# MCU.net
KiCad netlist of a schematic drawn in Altium Designer
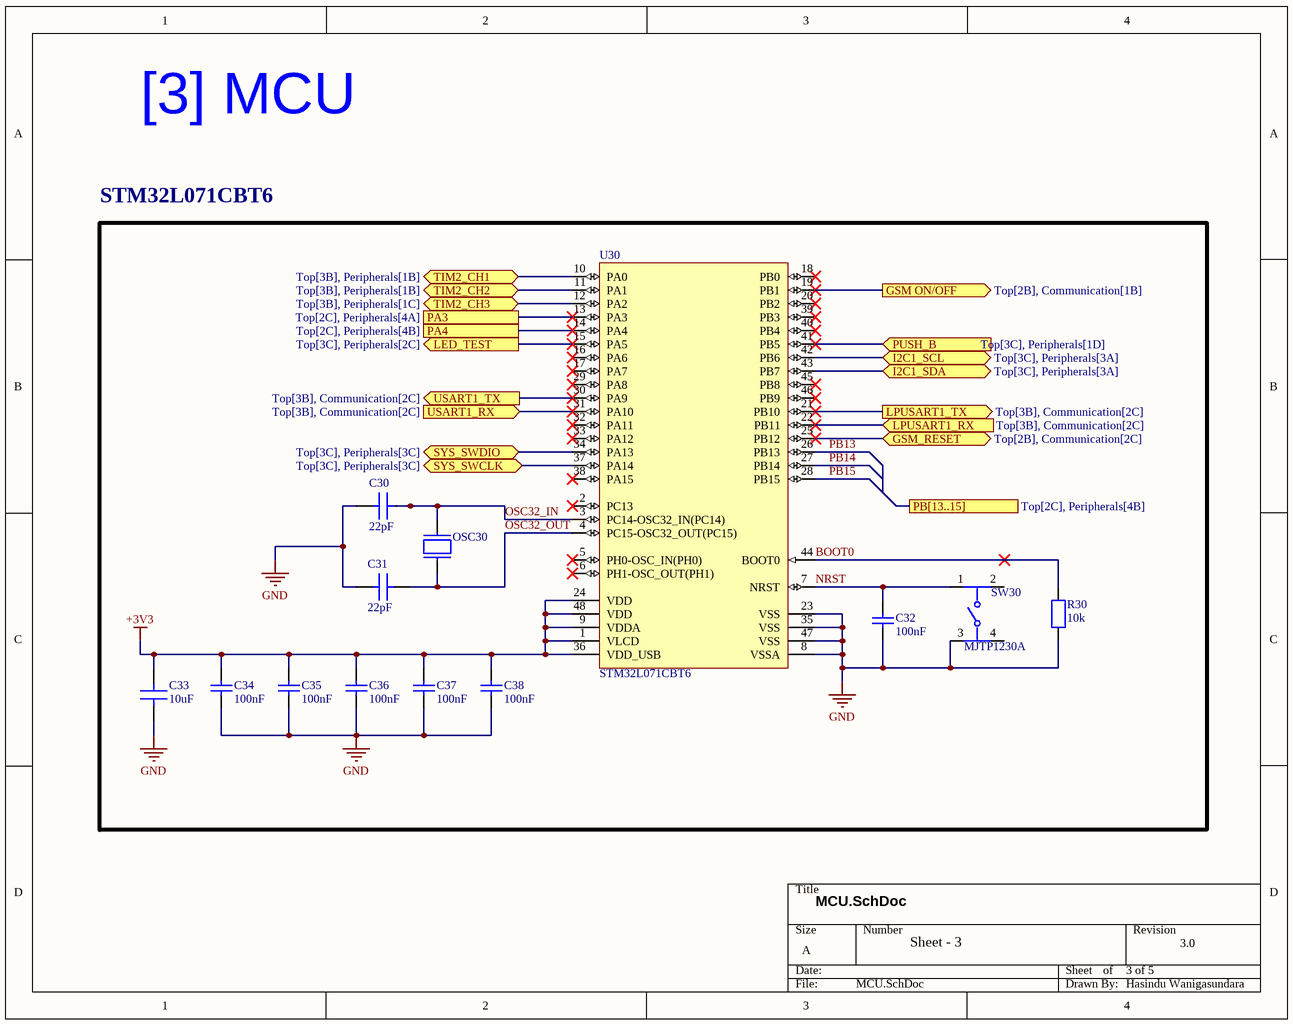
[diagram p0: MCU.SchDoc]

(export (version "E")
  (design (tool "Eeschema 10.0.6"))
  (components
    (comp (ref "C30")
      (value "22pF")
      (footprint "CAP_1206")
      (description "SMD 3.2mm × 1.6mm size capacitor (1206)")
      (libsource (lib "EDR - Water Meter") (part "CAP_1206"))
    )
    (comp (ref "C31")
      (value "22pF")
      (footprint "CAP_1206")
      (description "SMD 3.2mm × 1.6mm size capacitor (1206)")
      (libsource (lib "EDR - Water Meter") (part "CAP_1206"))
    )
    (comp (ref "C32")
      (value "100nF")
      (footprint "CAPC2013X140X50NL20T25")
      (fields
        (field (name "PART NUMBER") "0805YD105MAT2A")
        (field (name "MANUFACTURER") "AVX Interconnect / Elco")
      )
      (libsource (lib "Altium Content Vault") (part "CAP"))
    )
    (comp (ref "C33")
      (value "10uF")
      (footprint "CAP_1206")
      (description "SMD 3.2mm × 1.6mm size capacitor (1206)")
      (libsource (lib "EDR - Water Meter") (part "CAP_1206"))
    )
    (comp (ref "C34")
      (value "100nF")
      (footprint "CAPC2013X140X50NL20T25")
      (fields
        (field (name "PART NUMBER") "0805YD105MAT2A")
        (field (name "MANUFACTURER") "AVX Interconnect / Elco")
      )
      (libsource (lib "Altium Content Vault") (part "CAP"))
    )
    (comp (ref "C35")
      (value "100nF")
      (footprint "CAPC2013X140X50NL20T25")
      (fields
        (field (name "PART NUMBER") "0805YD105MAT2A")
        (field (name "MANUFACTURER") "AVX Interconnect / Elco")
      )
      (libsource (lib "Altium Content Vault") (part "CAP"))
    )
    (comp (ref "C36")
      (value "100nF")
      (footprint "CAPC2013X140X50NL20T25")
      (fields
        (field (name "PART NUMBER") "0805YD105MAT2A")
        (field (name "MANUFACTURER") "AVX Interconnect / Elco")
      )
      (libsource (lib "Altium Content Vault") (part "CAP"))
    )
    (comp (ref "C37")
      (value "100nF")
      (footprint "CAPC2013X140X50NL20T25")
      (fields
        (field (name "PART NUMBER") "0805YD105MAT2A")
        (field (name "MANUFACTURER") "AVX Interconnect / Elco")
      )
      (libsource (lib "Altium Content Vault") (part "CAP"))
    )
    (comp (ref "C38")
      (value "100nF")
      (footprint "CAPC2013X140X50NL20T25")
      (fields
        (field (name "PART NUMBER") "0805YD105MAT2A")
        (field (name "MANUFACTURER") "AVX Interconnect / Elco")
      )
      (libsource (lib "Altium Content Vault") (part "CAP"))
    )
    (comp (ref "OSC30")
      (value "CRYSTAL OSC")
      (footprint "Crystal_OSC")
      (description "CRYSTAL 32.768kHz 12.5pF SMD")
      (libsource (lib "EDR - Water Meter") (part "CRYSTAL OSC"))
    )
    (comp (ref "R30")
      (value "10k")
      (footprint "RES_1206")
      (description "SMD 3.2mm × 1.6mm size resistor (1206)")
      (libsource (lib "EDR - Water Meter") (part "RES_1206"))
    )
    (comp (ref "SW30")
      (value "MJTP1230A")
      (footprint "FP-MJTP1230A-MFG")
      (description "SWITCH TACTILE SPST-NO 0.05A 12V")
      (libsource (lib "Altium Content Vault") (part "1adf0dd01260c80cf25a44bfd6b99ba"))
    )
    (comp (ref "U30")
      (value "STM32L071CBT6")
      (footprint "STM-LQFP48_M")
      (description "ARM Cortex-M0+ 32 Bit 32MHz 37 LQFP-48(7x7) Microcontrollers RoHS")
      (libsource (lib "Altium Content Vault") (part "MC-ARM-STM32L073-LQFP48"))
    )
  )
  (nets
    (net (code "1") (name "+3V3") (class "Default")
      (node (ref "C33") (pin "2") (pintype "passive"))
      (node (ref "C34") (pin "2") (pinfunction "2_2") (pintype "passive"))
      (node (ref "C35") (pin "2") (pinfunction "2_2") (pintype "passive"))
      (node (ref "C36") (pin "2") (pinfunction "2_2") (pintype "passive"))
      (node (ref "C37") (pin "2") (pinfunction "2_2") (pintype "passive"))
      (node (ref "C38") (pin "2") (pinfunction "2_2") (pintype "passive"))
      (node (ref "U30") (pin "1") (pinfunction "VLCD_1") (pintype "power_in"))
      (node (ref "U30") (pin "24") (pinfunction "VDD_24") (pintype "power_in"))
      (node (ref "U30") (pin "36") (pinfunction "VDD_USB_36") (pintype "power_in"))
      (node (ref "U30") (pin "48") (pinfunction "VDD_48") (pintype "power_in"))
      (node (ref "U30") (pin "9") (pinfunction "VDDA_9") (pintype "power_in"))
    )
    (net (code "3") (name "/BOOT0") (class "Default")
      (node (ref "R30") (pin "1") (pintype "passive"))
      (node (ref "U30") (pin "44") (pinfunction "BOOT0_44") (pintype "input"))
    )
    (net (code "4") (name "/GSM ON{slash}OFF") (class "Default")
      (node (ref "U30") (pin "19") (pinfunction "PB1_19") (pintype "bidirectional+no_connect"))
    )
    (net (code "5") (name "/GSM_RESET") (class "Default")
      (node (ref "U30") (pin "25") (pinfunction "PB12_25") (pintype "bidirectional+no_connect"))
    )
    (net (code "6") (name "/I2C1_SCL") (class "Default")
      (node (ref "U30") (pin "42") (pinfunction "PB6_42") (pintype "bidirectional"))
    )
    (net (code "7") (name "/I2C1_SDA") (class "Default")
      (node (ref "U30") (pin "43") (pinfunction "PB7_43") (pintype "bidirectional"))
    )
    (net (code "8") (name "/LED_TEST") (class "Default")
      (node (ref "U30") (pin "15") (pinfunction "PA5_15") (pintype "bidirectional+no_connect"))
    )
    (net (code "9") (name "/LPUSART1_RX") (class "Default")
      (node (ref "U30") (pin "22") (pinfunction "PB11_22") (pintype "bidirectional+no_connect"))
    )
    (net (code "10") (name "/LPUSART1_TX") (class "Default")
      (node (ref "U30") (pin "21") (pinfunction "PB10_21") (pintype "bidirectional+no_connect"))
    )
    (net (code "11") (name "/NRST") (class "Default")
      (node (ref "C32") (pin "2") (pinfunction "2_2") (pintype "passive"))
      (node (ref "SW30") (pin "1") (pinfunction "1_1") (pintype "passive"))
      (node (ref "U30") (pin "7") (pinfunction "NRST_7") (pintype "bidirectional"))
    )
    (net (code "12") (name "/OSC32_IN") (class "Default")
      (node (ref "C30") (pin "1") (pintype "passive"))
      (node (ref "OSC30") (pin "2") (pintype "passive"))
      (node (ref "U30") (pin "3") (pinfunction "PC14-OSC32_IN(PC14)_3") (pintype "bidirectional"))
    )
    (net (code "13") (name "/OSC32_OUT") (class "Default")
      (node (ref "C31") (pin "2") (pintype "passive"))
      (node (ref "OSC30") (pin "1") (pintype "passive"))
      (node (ref "U30") (pin "4") (pinfunction "PC15-OSC32_OUT(PC15)_4") (pintype "bidirectional"))
    )
    (net (code "14") (name "/PA3") (class "Default")
      (node (ref "U30") (pin "13") (pinfunction "PA3_13") (pintype "bidirectional+no_connect"))
    )
    (net (code "15") (name "/PA4") (class "Default")
      (node (ref "U30") (pin "14") (pinfunction "PA4_14") (pintype "bidirectional+no_connect"))
    )
    (net (code "16") (name "/PB13") (class "Default")
      (node (ref "U30") (pin "26") (pinfunction "PB13_26") (pintype "bidirectional"))
    )
    (net (code "17") (name "/PB14") (class "Default")
      (node (ref "U30") (pin "27") (pinfunction "PB14_27") (pintype "bidirectional"))
    )
    (net (code "18") (name "/PB15") (class "Default")
      (node (ref "U30") (pin "28") (pinfunction "PB15_28") (pintype "bidirectional"))
    )
    (net (code "20") (name "/PUSH_B") (class "Default")
      (node (ref "U30") (pin "41") (pinfunction "PB5_41") (pintype "bidirectional+no_connect"))
    )
    (net (code "21") (name "/SYS_SWCLK") (class "Default")
      (node (ref "U30") (pin "37") (pinfunction "PA14_37") (pintype "bidirectional"))
    )
    (net (code "22") (name "/SYS_SWDIO") (class "Default")
      (node (ref "U30") (pin "34") (pinfunction "PA13_34") (pintype "bidirectional"))
    )
    (net (code "23") (name "/TIM2_CH1") (class "Default")
      (node (ref "U30") (pin "10") (pinfunction "PA0_10") (pintype "bidirectional"))
    )
    (net (code "24") (name "/TIM2_CH2") (class "Default")
      (node (ref "U30") (pin "11") (pinfunction "PA1_11") (pintype "bidirectional"))
    )
    (net (code "25") (name "/TIM2_CH3") (class "Default")
      (node (ref "U30") (pin "12") (pinfunction "PA2_12") (pintype "bidirectional"))
    )
    (net (code "26") (name "/USART1_RX") (class "Default")
      (node (ref "U30") (pin "31") (pinfunction "PA10_31") (pintype "bidirectional+no_connect"))
    )
    (net (code "27") (name "/USART1_TX") (class "Default")
      (node (ref "U30") (pin "30") (pinfunction "PA9_30") (pintype "bidirectional+no_connect"))
    )
    (net (code "28") (name "GND") (class "Default")
      (node (ref "C30") (pin "2") (pintype "passive"))
      (node (ref "C31") (pin "1") (pintype "passive"))
      (node (ref "C32") (pin "1") (pinfunction "1_1") (pintype "passive"))
      (node (ref "C33") (pin "1") (pintype "passive"))
      (node (ref "C34") (pin "1") (pinfunction "1_1") (pintype "passive"))
      (node (ref "C35") (pin "1") (pinfunction "1_1") (pintype "passive"))
      (node (ref "C36") (pin "1") (pinfunction "1_1") (pintype "passive"))
      (node (ref "C37") (pin "1") (pinfunction "1_1") (pintype "passive"))
      (node (ref "C38") (pin "1") (pinfunction "1_1") (pintype "passive"))
      (node (ref "R30") (pin "2") (pintype "passive"))
      (node (ref "SW30") (pin "3") (pinfunction "3_3") (pintype "passive"))
      (node (ref "U30") (pin "23") (pinfunction "VSS_23") (pintype "power_in"))
      (node (ref "U30") (pin "35") (pinfunction "VSS_35") (pintype "power_in"))
      (node (ref "U30") (pin "47") (pinfunction "VSS_47") (pintype "power_in"))
      (node (ref "U30") (pin "8") (pinfunction "VSSA_8") (pintype "power_in"))
    )
    (net (code "29") (name "unconnected-(SW30-Pad2)") (class "Default")
      (node (ref "SW30") (pin "2") (pinfunction "2_2") (pintype "passive"))
    )
    (net (code "30") (name "unconnected-(SW30-Pad4)") (class "Default")
      (node (ref "SW30") (pin "4") (pinfunction "4_4") (pintype "passive"))
    )
    (net (code "31") (name "unconnected-(U30-PA6-Pad16)") (class "Default")
      (node (ref "U30") (pin "16") (pinfunction "PA6_16") (pintype "bidirectional+no_connect"))
    )
    (net (code "32") (name "unconnected-(U30-PA7-Pad17)") (class "Default")
      (node (ref "U30") (pin "17") (pinfunction "PA7_17") (pintype "bidirectional+no_connect"))
    )
    (net (code "33") (name "unconnected-(U30-PA8-Pad29)") (class "Default")
      (node (ref "U30") (pin "29") (pinfunction "PA8_29") (pintype "bidirectional+no_connect"))
    )
    (net (code "34") (name "unconnected-(U30-PA11-Pad32)") (class "Default")
      (node (ref "U30") (pin "32") (pinfunction "PA11_32") (pintype "bidirectional+no_connect"))
    )
    (net (code "35") (name "unconnected-(U30-PA12-Pad33)") (class "Default")
      (node (ref "U30") (pin "33") (pinfunction "PA12_33") (pintype "bidirectional+no_connect"))
    )
    (net (code "36") (name "unconnected-(U30-PA15-Pad38)") (class "Default")
      (node (ref "U30") (pin "38") (pinfunction "PA15_38") (pintype "bidirectional+no_connect"))
    )
    (net (code "37") (name "unconnected-(U30-PB0-Pad18)") (class "Default")
      (node (ref "U30") (pin "18") (pinfunction "PB0_18") (pintype "bidirectional+no_connect"))
    )
    (net (code "38") (name "unconnected-(U30-PB2-Pad20)") (class "Default")
      (node (ref "U30") (pin "20") (pinfunction "PB2_20") (pintype "bidirectional+no_connect"))
    )
    (net (code "39") (name "unconnected-(U30-PB3-Pad39)") (class "Default")
      (node (ref "U30") (pin "39") (pinfunction "PB3_39") (pintype "bidirectional+no_connect"))
    )
    (net (code "40") (name "unconnected-(U30-PB4-Pad40)") (class "Default")
      (node (ref "U30") (pin "40") (pinfunction "PB4_40") (pintype "bidirectional+no_connect"))
    )
    (net (code "41") (name "unconnected-(U30-PB8-Pad45)") (class "Default")
      (node (ref "U30") (pin "45") (pinfunction "PB8_45") (pintype "bidirectional+no_connect"))
    )
    (net (code "42") (name "unconnected-(U30-PB9-Pad46)") (class "Default")
      (node (ref "U30") (pin "46") (pinfunction "PB9_46") (pintype "bidirectional+no_connect"))
    )
    (net (code "43") (name "unconnected-(U30-PC13-Pad2)") (class "Default")
      (node (ref "U30") (pin "2") (pinfunction "PC13_2") (pintype "bidirectional+no_connect"))
    )
    (net (code "44") (name "unconnected-(U30-PH0-OSC_IN(PH0)-Pad5)") (class "Default")
      (node (ref "U30") (pin "5") (pinfunction "PH0-OSC_IN(PH0)_5") (pintype "bidirectional+no_connect"))
    )
    (net (code "45") (name "unconnected-(U30-PH1-OSC_OUT(PH1)-Pad6)") (class "Default")
      (node (ref "U30") (pin "6") (pinfunction "PH1-OSC_OUT(PH1)_6") (pintype "bidirectional+no_connect"))
    )
  )
)
